# controller-board.net
KiCad netlist of a schematic drawn in EAGLE
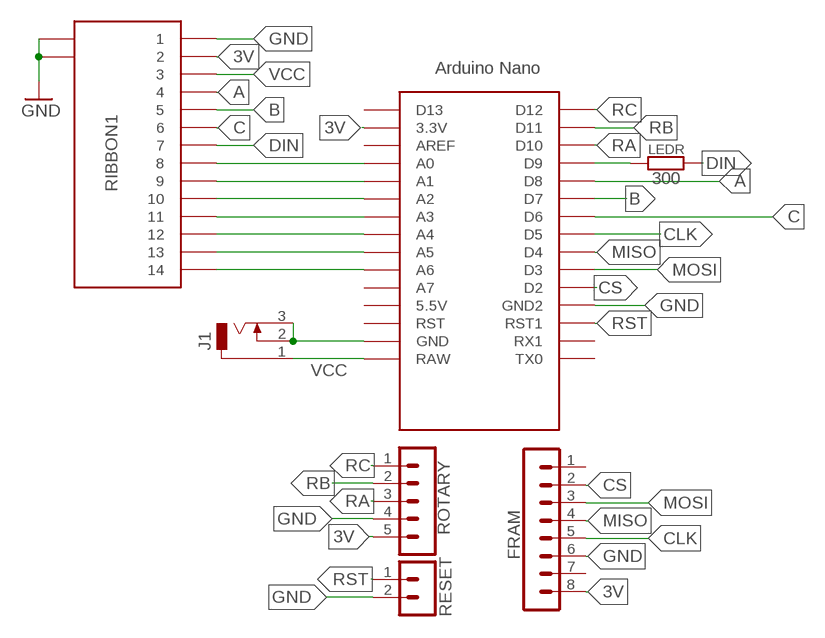
[diagram p0: schematic, sheet 1]

(export (version "E")
  (design (tool "Eeschema 10.0.6"))
  (components
    (comp (ref "FRAM")
      (value "MB85RS2MTA")
      (footprint "eagle-import:MA08-1")
      (libsource (lib "eagle-import") (part "MA08-1"))
    )
    (comp (ref "J1")
      (value "DCJ0202")
      (footprint "eagle-import:DCJ0202")
      (libsource (lib "eagle-import") (part "DCJ0202"))
    )
    (comp (ref "LEDR")
      (value "300")
      (footprint "eagle-import:0207_10")
      (libsource (lib "eagle-import") (part "R-EU_0207/10"))
    )
    (comp (ref "RESET")
      (value "B2B-PH-K")
      (footprint "eagle-import:B2B-PH-K")
      (libsource (lib "eagle-import") (part "B2B-PH-K"))
    )
    (comp (ref "RIBBON1")
      (value "686114148922")
      (footprint "eagle-import:686114148922")
      (fields (field (name "MOUSER_PART_NUMBER") "710-686114148922"))
      (libsource (lib "eagle-import") (part "686114148922"))
    )
    (comp (ref "ROTARY")
      (value "B5B-PH-K")
      (footprint "eagle-import:B5B-PH-K")
      (libsource (lib "eagle-import") (part "B5B-PH-K"))
    )
    (comp (ref "U$1")
      (value "NANO")
      (footprint "eagle-import:NANO")
      (libsource (lib "eagle-import") (part "NANO"))
    )
  )
  (nets
    (net (code "1") (name "3V") (class "Default")
      (node (ref "FRAM") (pin "8") (pinfunction "8_8") (pintype "passive"))
      (node (ref "RIBBON1") (pin "2") (pinfunction "2_2") (pintype "bidirectional"))
      (node (ref "ROTARY") (pin "5") (pinfunction "5_5") (pintype "passive"))
      (node (ref "U$1") (pin "3.3V") (pinfunction "3.3V_3.3V") (pintype "bidirectional"))
    )
    (net (code "2") (name "A") (class "Default")
      (node (ref "RIBBON1") (pin "4") (pinfunction "4_4") (pintype "bidirectional"))
      (node (ref "U$1") (pin "D8") (pinfunction "D8_D8") (pintype "bidirectional"))
    )
    (net (code "3") (name "B") (class "Default")
      (node (ref "RIBBON1") (pin "5") (pinfunction "5_5") (pintype "bidirectional"))
      (node (ref "U$1") (pin "D7") (pinfunction "D7_D7") (pintype "bidirectional"))
    )
    (net (code "4") (name "C") (class "Default")
      (node (ref "RIBBON1") (pin "6") (pinfunction "6_6") (pintype "bidirectional"))
      (node (ref "U$1") (pin "D6") (pinfunction "D6_D6") (pintype "bidirectional"))
    )
    (net (code "5") (name "CLK") (class "Default")
      (node (ref "FRAM") (pin "5") (pinfunction "5_5") (pintype "passive"))
      (node (ref "U$1") (pin "D5") (pinfunction "D5_D5") (pintype "bidirectional"))
    )
    (net (code "6") (name "CS") (class "Default")
      (node (ref "FRAM") (pin "2") (pinfunction "2_2") (pintype "passive"))
      (node (ref "U$1") (pin "D2") (pinfunction "D2_D2") (pintype "bidirectional"))
    )
    (net (code "7") (name "DIN") (class "Default")
      (node (ref "LEDR") (pin "2") (pinfunction "2_2") (pintype "passive"))
      (node (ref "RIBBON1") (pin "7") (pinfunction "7_7") (pintype "bidirectional"))
    )
    (net (code "8") (name "GND") (class "Default")
      (node (ref "FRAM") (pin "6") (pinfunction "6_6") (pintype "passive"))
      (node (ref "J1") (pin "2") (pinfunction "2_2") (pintype "passive"))
      (node (ref "J1") (pin "3") (pinfunction "3_3") (pintype "passive"))
      (node (ref "RESET") (pin "2") (pinfunction "2_2") (pintype "passive"))
      (node (ref "RIBBON1") (pin "1") (pinfunction "1_1") (pintype "bidirectional"))
      (node (ref "RIBBON1") (pin "MP1") (pinfunction "MP1_MP1") (pintype "bidirectional"))
      (node (ref "RIBBON1") (pin "MP2") (pinfunction "MP2_MP2") (pintype "bidirectional"))
      (node (ref "ROTARY") (pin "4") (pinfunction "4_4") (pintype "passive"))
      (node (ref "U$1") (pin "GND") (pinfunction "GND_GND") (pintype "bidirectional"))
      (node (ref "U$1") (pin "GND1") (pinfunction "GND2_GND1") (pintype "bidirectional"))
    )
    (net (code "9") (name "MISO") (class "Default")
      (node (ref "FRAM") (pin "4") (pinfunction "4_4") (pintype "passive"))
      (node (ref "U$1") (pin "D4") (pinfunction "D4_D4") (pintype "bidirectional"))
    )
    (net (code "10") (name "MOSI") (class "Default")
      (node (ref "FRAM") (pin "3") (pinfunction "3_3") (pintype "passive"))
      (node (ref "U$1") (pin "D3") (pinfunction "D3_D3") (pintype "bidirectional"))
    )
    (net (code "11") (name "Net-(LEDR-Pad1)") (class "Default")
      (node (ref "LEDR") (pin "1") (pinfunction "1_1") (pintype "passive"))
      (node (ref "U$1") (pin "D9") (pinfunction "D9_D9") (pintype "bidirectional"))
    )
    (net (code "12") (name "Net-(RIBBON1-Pad8)") (class "Default")
      (node (ref "RIBBON1") (pin "8") (pinfunction "8_8") (pintype "bidirectional"))
      (node (ref "U$1") (pin "A0") (pinfunction "A0_A0") (pintype "bidirectional"))
    )
    (net (code "13") (name "Net-(RIBBON1-Pad9)") (class "Default")
      (node (ref "RIBBON1") (pin "9") (pinfunction "9_9") (pintype "bidirectional"))
      (node (ref "U$1") (pin "A1") (pinfunction "A1_A1") (pintype "bidirectional"))
    )
    (net (code "14") (name "Net-(RIBBON1-Pad10)") (class "Default")
      (node (ref "RIBBON1") (pin "10") (pinfunction "10_10") (pintype "bidirectional"))
      (node (ref "U$1") (pin "A2") (pinfunction "A2_A2") (pintype "bidirectional"))
    )
    (net (code "15") (name "Net-(RIBBON1-Pad11)") (class "Default")
      (node (ref "RIBBON1") (pin "11") (pinfunction "11_11") (pintype "bidirectional"))
      (node (ref "U$1") (pin "A3") (pinfunction "A3_A3") (pintype "bidirectional"))
    )
    (net (code "16") (name "Net-(RIBBON1-Pad12)") (class "Default")
      (node (ref "RIBBON1") (pin "12") (pinfunction "12_12") (pintype "bidirectional"))
      (node (ref "U$1") (pin "A4") (pinfunction "A4_A4") (pintype "bidirectional"))
    )
    (net (code "17") (name "Net-(RIBBON1-Pad13)") (class "Default")
      (node (ref "RIBBON1") (pin "13") (pinfunction "13_13") (pintype "bidirectional"))
      (node (ref "U$1") (pin "A5") (pinfunction "A5_A5") (pintype "bidirectional"))
    )
    (net (code "18") (name "Net-(RIBBON1-Pad14)") (class "Default")
      (node (ref "RIBBON1") (pin "14") (pinfunction "14_14") (pintype "bidirectional"))
      (node (ref "U$1") (pin "A6") (pinfunction "A6_A6") (pintype "bidirectional"))
    )
    (net (code "19") (name "RA") (class "Default")
      (node (ref "ROTARY") (pin "3") (pinfunction "3_3") (pintype "passive"))
      (node (ref "U$1") (pin "D10") (pinfunction "D10_D10") (pintype "bidirectional"))
    )
    (net (code "20") (name "RB") (class "Default")
      (node (ref "ROTARY") (pin "2") (pinfunction "2_2") (pintype "passive"))
      (node (ref "U$1") (pin "D11") (pinfunction "D11_D11") (pintype "bidirectional"))
    )
    (net (code "21") (name "RC") (class "Default")
      (node (ref "ROTARY") (pin "1") (pinfunction "1_1") (pintype "passive"))
      (node (ref "U$1") (pin "D12") (pinfunction "D12_D12") (pintype "bidirectional"))
    )
    (net (code "22") (name "RST") (class "Default")
      (node (ref "RESET") (pin "1") (pinfunction "1_1") (pintype "passive"))
      (node (ref "U$1") (pin "RST1") (pinfunction "RST1_RST1") (pintype "bidirectional"))
    )
    (net (code "23") (name "VCC") (class "Default")
      (node (ref "J1") (pin "1") (pinfunction "1_1") (pintype "passive"))
      (node (ref "RIBBON1") (pin "3") (pinfunction "3_3") (pintype "bidirectional"))
      (node (ref "U$1") (pin "RAW") (pinfunction "RAW_RAW") (pintype "bidirectional"))
    )
    (net (code "24") (name "unconnected-(FRAM-Pad1)") (class "Default")
      (node (ref "FRAM") (pin "1") (pinfunction "1_1") (pintype "passive"))
    )
    (net (code "25") (name "unconnected-(FRAM-Pad7)") (class "Default")
      (node (ref "FRAM") (pin "7") (pinfunction "7_7") (pintype "passive"))
    )
    (net (code "26") (name "unconnected-(U$1-5.5V-Pad5V)") (class "Default")
      (node (ref "U$1") (pin "5V") (pinfunction "5.5V_5V") (pintype "bidirectional"))
    )
    (net (code "27") (name "unconnected-(U$1-PadA7)") (class "Default")
      (node (ref "U$1") (pin "A7") (pinfunction "A7_A7") (pintype "bidirectional"))
    )
    (net (code "28") (name "unconnected-(U$1-PadAREF)") (class "Default")
      (node (ref "U$1") (pin "AREF") (pinfunction "AREF_AREF") (pintype "bidirectional"))
    )
    (net (code "29") (name "unconnected-(U$1-PadD13)") (class "Default")
      (node (ref "U$1") (pin "D13") (pinfunction "D13_D13") (pintype "bidirectional"))
    )
    (net (code "30") (name "unconnected-(U$1-PadICSP1)") (class "Default")
      (node (ref "U$1") (pin "ICSP1") (pinfunction "ICSP1_ICSP1") (pintype "bidirectional"))
    )
    (net (code "31") (name "unconnected-(U$1-PadICSP2)") (class "Default")
      (node (ref "U$1") (pin "ICSP2") (pinfunction "ICSP2_ICSP2") (pintype "bidirectional"))
    )
    (net (code "32") (name "unconnected-(U$1-PadICSP3)") (class "Default")
      (node (ref "U$1") (pin "ICSP3") (pinfunction "ICSP3_ICSP3") (pintype "bidirectional"))
    )
    (net (code "33") (name "unconnected-(U$1-PadICSP4)") (class "Default")
      (node (ref "U$1") (pin "ICSP4") (pinfunction "ICSP4_ICSP4") (pintype "bidirectional"))
    )
    (net (code "34") (name "unconnected-(U$1-PadICSP5)") (class "Default")
      (node (ref "U$1") (pin "ICSP5") (pinfunction "ICSP5_ICSP5") (pintype "bidirectional"))
    )
    (net (code "35") (name "unconnected-(U$1-PadICSP6)") (class "Default")
      (node (ref "U$1") (pin "ICSP6") (pinfunction "ICSP6_ICSP6") (pintype "bidirectional"))
    )
    (net (code "36") (name "unconnected-(U$1-PadRST)") (class "Default")
      (node (ref "U$1") (pin "RST") (pinfunction "RST_RST") (pintype "bidirectional"))
    )
    (net (code "37") (name "unconnected-(U$1-PadRX1)") (class "Default")
      (node (ref "U$1") (pin "RX1") (pinfunction "RX1_RX1") (pintype "bidirectional"))
    )
    (net (code "38") (name "unconnected-(U$1-PadTX0)") (class "Default")
      (node (ref "U$1") (pin "TX0") (pinfunction "TX0_TX0") (pintype "bidirectional"))
    )
  )
)
